# Sheet1.net
KiCad netlist of a schematic drawn in Altium Designer
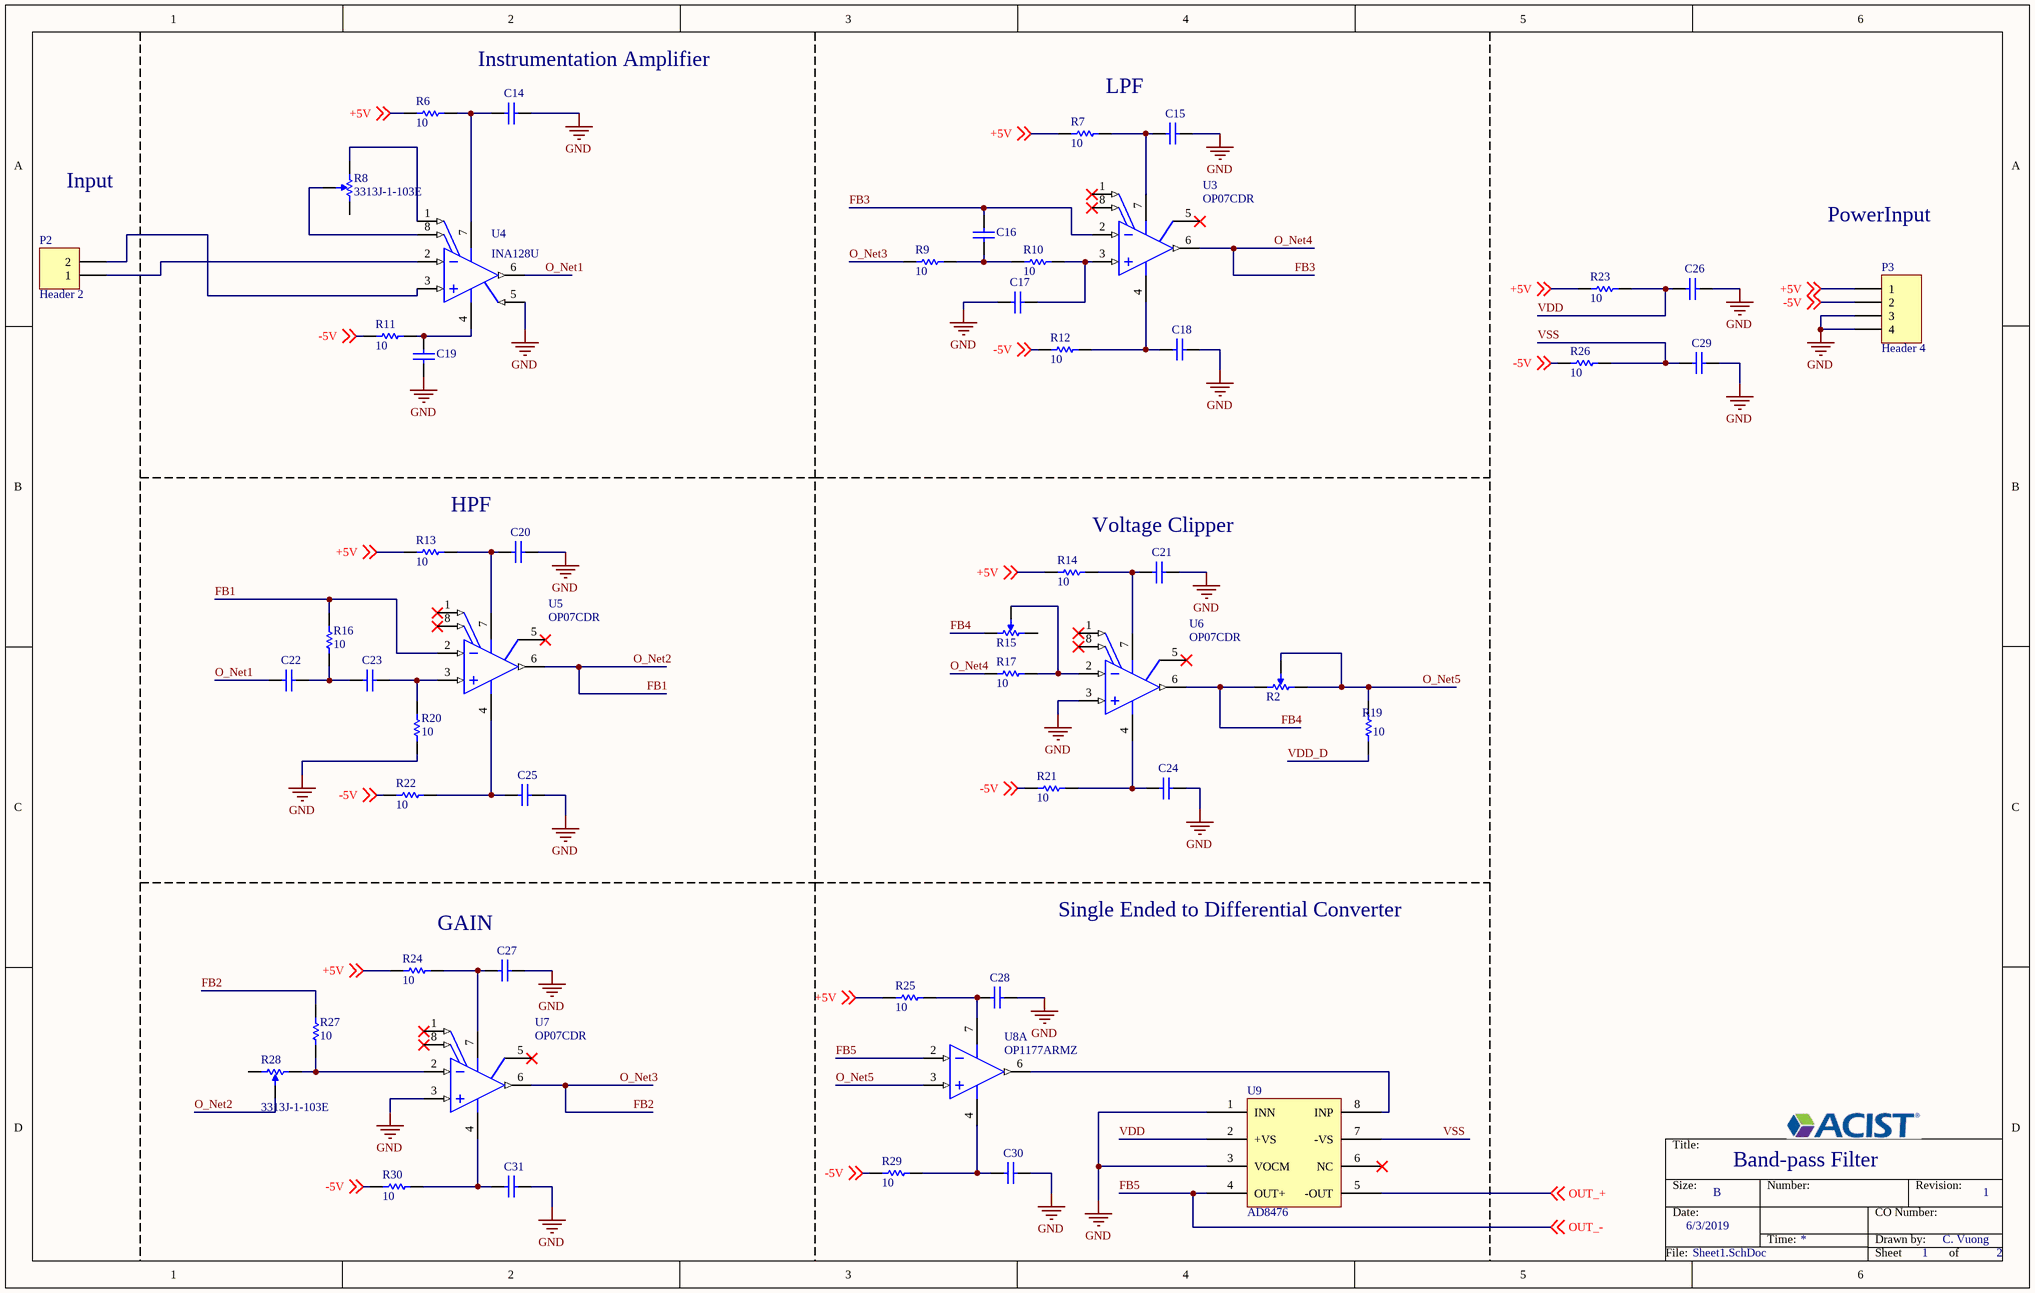
[diagram p0: Sheet1.SchDoc]

(export (version "E")
  (design (tool "Eeschema 10.0.6"))
  (components
    (comp (ref "C14")
      (value "C1608X5R1A106K080AC")
      (footprint "CAPC1608X90X20ML10")
      (description "Chip Capacitor, 10 uF, +/- 10%, 10 V, -55 to 85 degC, 0603 (1608 Metric), RoHS, Tape and Reel")
      (fields
        (field (name "PCN PART NUMBER") "MLCCPartNumberChange30/Nov/2012")
        (field (name "TOLERANCE") "±10%")
      )
      (libsource (lib "Altium Content Vault") (part "CAP-NP-2"))
    )
    (comp (ref "C15")
      (value "C1608X5R1A106K080AC")
      (footprint "CAPC1608X90X20ML10")
      (description "Chip Capacitor, 10 uF, +/- 10%, 10 V, -55 to 85 degC, 0603 (1608 Metric), RoHS, Tape and Reel")
      (fields
        (field (name "PCN PART NUMBER") "MLCCPartNumberChange30/Nov/2012")
        (field (name "TOLERANCE") "±10%")
      )
      (libsource (lib "Altium Content Vault") (part "CAP-NP-2"))
    )
    (comp (ref "C16")
      (value "C1608X5R1A106K080AC")
      (footprint "CAPC1608X90X20ML10")
      (description "Chip Capacitor, 10 uF, +/- 10%, 10 V, -55 to 85 degC, 0603 (1608 Metric), RoHS, Tape and Reel")
      (fields
        (field (name "PCN PART NUMBER") "MLCCPartNumberChange30/Nov/2012")
        (field (name "TOLERANCE") "±10%")
      )
      (libsource (lib "Altium Content Vault") (part "CAP-NP-2"))
    )
    (comp (ref "C17")
      (value "C1608X5R1A106K080AC")
      (footprint "CAPC1608X90X20ML10")
      (description "Chip Capacitor, 10 uF, +/- 10%, 10 V, -55 to 85 degC, 0603 (1608 Metric), RoHS, Tape and Reel")
      (fields
        (field (name "PCN PART NUMBER") "MLCCPartNumberChange30/Nov/2012")
        (field (name "TOLERANCE") "±10%")
      )
      (libsource (lib "Altium Content Vault") (part "CAP-NP-2"))
    )
    (comp (ref "C18")
      (value "C1608X5R1A106K080AC")
      (footprint "CAPC1608X90X20ML10")
      (description "Chip Capacitor, 10 uF, +/- 10%, 10 V, -55 to 85 degC, 0603 (1608 Metric), RoHS, Tape and Reel")
      (fields
        (field (name "PCN PART NUMBER") "MLCCPartNumberChange30/Nov/2012")
        (field (name "TOLERANCE") "±10%")
      )
      (libsource (lib "Altium Content Vault") (part "CAP-NP-2"))
    )
    (comp (ref "C19")
      (value "C1608X5R1A106K080AC")
      (footprint "CAPC1608X90X20ML10")
      (description "Chip Capacitor, 10 uF, +/- 10%, 10 V, -55 to 85 degC, 0603 (1608 Metric), RoHS, Tape and Reel")
      (fields
        (field (name "PCN PART NUMBER") "MLCCPartNumberChange30/Nov/2012")
        (field (name "TOLERANCE") "±10%")
      )
      (libsource (lib "Altium Content Vault") (part "CAP-NP-2"))
    )
    (comp (ref "C20")
      (value "C1608X5R1A106K080AC")
      (footprint "CAPC1608X90X20ML10")
      (description "Chip Capacitor, 10 uF, +/- 10%, 10 V, -55 to 85 degC, 0603 (1608 Metric), RoHS, Tape and Reel")
      (fields
        (field (name "PCN PART NUMBER") "MLCCPartNumberChange30/Nov/2012")
        (field (name "TOLERANCE") "±10%")
      )
      (libsource (lib "Altium Content Vault") (part "CAP-NP-2"))
    )
    (comp (ref "C21")
      (value "C1608X5R1A106K080AC")
      (footprint "CAPC1608X90X20ML10")
      (description "Chip Capacitor, 10 uF, +/- 10%, 10 V, -55 to 85 degC, 0603 (1608 Metric), RoHS, Tape and Reel")
      (fields
        (field (name "PCN PART NUMBER") "MLCCPartNumberChange30/Nov/2012")
        (field (name "TOLERANCE") "±10%")
      )
      (libsource (lib "Altium Content Vault") (part "CAP-NP-2"))
    )
    (comp (ref "C22")
      (value "C1608X5R1A106K080AC")
      (footprint "CAPC1608X90X20ML10")
      (description "Chip Capacitor, 10 uF, +/- 10%, 10 V, -55 to 85 degC, 0603 (1608 Metric), RoHS, Tape and Reel")
      (fields
        (field (name "PCN PART NUMBER") "MLCCPartNumberChange30/Nov/2012")
        (field (name "TOLERANCE") "±10%")
      )
      (libsource (lib "Altium Content Vault") (part "CAP-NP-2"))
    )
    (comp (ref "C23")
      (value "C1608X5R1A106K080AC")
      (footprint "CAPC1608X90X20ML10")
      (description "Chip Capacitor, 10 uF, +/- 10%, 10 V, -55 to 85 degC, 0603 (1608 Metric), RoHS, Tape and Reel")
      (fields
        (field (name "PCN PART NUMBER") "MLCCPartNumberChange30/Nov/2012")
        (field (name "TOLERANCE") "±10%")
      )
      (libsource (lib "Altium Content Vault") (part "CAP-NP-2"))
    )
    (comp (ref "C24")
      (value "C1608X5R1A106K080AC")
      (footprint "CAPC1608X90X20ML10")
      (description "Chip Capacitor, 10 uF, +/- 10%, 10 V, -55 to 85 degC, 0603 (1608 Metric), RoHS, Tape and Reel")
      (fields
        (field (name "PCN PART NUMBER") "MLCCPartNumberChange30/Nov/2012")
        (field (name "TOLERANCE") "±10%")
      )
      (libsource (lib "Altium Content Vault") (part "CAP-NP-2"))
    )
    (comp (ref "C25")
      (value "C1608X5R1A106K080AC")
      (footprint "CAPC1608X90X20ML10")
      (description "Chip Capacitor, 10 uF, +/- 10%, 10 V, -55 to 85 degC, 0603 (1608 Metric), RoHS, Tape and Reel")
      (fields
        (field (name "PCN PART NUMBER") "MLCCPartNumberChange30/Nov/2012")
        (field (name "TOLERANCE") "±10%")
      )
      (libsource (lib "Altium Content Vault") (part "CAP-NP-2"))
    )
    (comp (ref "C26")
      (value "C1608X5R1A106K080AC")
      (footprint "CAPC1608X90X20ML10")
      (description "Chip Capacitor, 10 uF, +/- 10%, 10 V, -55 to 85 degC, 0603 (1608 Metric), RoHS, Tape and Reel")
      (fields
        (field (name "PCN PART NUMBER") "MLCCPartNumberChange30/Nov/2012")
        (field (name "TOLERANCE") "±10%")
      )
      (libsource (lib "Altium Content Vault") (part "CAP-NP-2"))
    )
    (comp (ref "C27")
      (value "C1608X5R1A106K080AC")
      (footprint "CAPC1608X90X20ML10")
      (description "Chip Capacitor, 10 uF, +/- 10%, 10 V, -55 to 85 degC, 0603 (1608 Metric), RoHS, Tape and Reel")
      (fields
        (field (name "PCN PART NUMBER") "MLCCPartNumberChange30/Nov/2012")
        (field (name "TOLERANCE") "±10%")
      )
      (libsource (lib "Altium Content Vault") (part "CAP-NP-2"))
    )
    (comp (ref "C28")
      (value "C1608X5R1A106K080AC")
      (footprint "CAPC1608X90X20ML10")
      (description "Chip Capacitor, 10 uF, +/- 10%, 10 V, -55 to 85 degC, 0603 (1608 Metric), RoHS, Tape and Reel")
      (fields
        (field (name "PCN PART NUMBER") "MLCCPartNumberChange30/Nov/2012")
        (field (name "TOLERANCE") "±10%")
      )
      (libsource (lib "Altium Content Vault") (part "CAP-NP-2"))
    )
    (comp (ref "C29")
      (value "C1608X5R1A106K080AC")
      (footprint "CAPC1608X90X20ML10")
      (description "Chip Capacitor, 10 uF, +/- 10%, 10 V, -55 to 85 degC, 0603 (1608 Metric), RoHS, Tape and Reel")
      (fields
        (field (name "PCN PART NUMBER") "MLCCPartNumberChange30/Nov/2012")
        (field (name "TOLERANCE") "±10%")
      )
      (libsource (lib "Altium Content Vault") (part "CAP-NP-2"))
    )
    (comp (ref "C30")
      (value "C1608X5R1A106K080AC")
      (footprint "CAPC1608X90X20ML10")
      (description "Chip Capacitor, 10 uF, +/- 10%, 10 V, -55 to 85 degC, 0603 (1608 Metric), RoHS, Tape and Reel")
      (fields
        (field (name "PCN PART NUMBER") "MLCCPartNumberChange30/Nov/2012")
        (field (name "TOLERANCE") "±10%")
      )
      (libsource (lib "Altium Content Vault") (part "CAP-NP-2"))
    )
    (comp (ref "C31")
      (value "C1608X5R1A106K080AC")
      (footprint "CAPC1608X90X20ML10")
      (description "Chip Capacitor, 10 uF, +/- 10%, 10 V, -55 to 85 degC, 0603 (1608 Metric), RoHS, Tape and Reel")
      (fields
        (field (name "PCN PART NUMBER") "MLCCPartNumberChange30/Nov/2012")
        (field (name "TOLERANCE") "±10%")
      )
      (libsource (lib "Altium Content Vault") (part "CAP-NP-2"))
    )
    (comp (ref "P2")
      (value "Header 2")
      (footprint "HDR1X2")
      (description "Header, 2-Pin")
      (fields (field (name "PUBLISHER") "Altium Limited"))
      (libsource (lib "Miscellaneous Connectors") (part "Header 2"))
    )
    (comp (ref "P3")
      (value "Header 4")
      (footprint "HDR1X4")
      (description "Header, 4-Pin")
      (fields (field (name "PUBLISHER") "Altium Limited"))
      (libsource (lib "Miscellaneous Connectors") (part "Header 4"))
    )
    (comp (ref "R2")
      (value "3313J-1-103E")
      (footprint "BOUR-3313J-1_V")
      (description "Trimming Potentiometer, 10 KOhm, -55 to 125 degC, 3-Pin SMD, RoHS, Tape and Reel")
      (fields (field (name "MANUFACTURER") "Bourns"))
      (libsource (lib "Altium Content Vault") (part "RES-ADJ-3_A"))
    )
    (comp (ref "R6")
      (value "10")
      (footprint "RESC1608X50X30LL20T20")
      (fields (field (name "PART NUMBER") "RR0816P-241-D") (field (name "MANUFACTURER") "Susumu"))
      (libsource (lib "Altium Content Vault") (part "RES"))
    )
    (comp (ref "R7")
      (value "10")
      (footprint "RESC1608X50X30LL20T20")
      (fields (field (name "PART NUMBER") "RR0816P-241-D") (field (name "MANUFACTURER") "Susumu"))
      (libsource (lib "Altium Content Vault") (part "RES"))
    )
    (comp (ref "R8")
      (value "3313J-1-103E")
      (footprint "BOUR-3313J-1_V")
      (description "Trimming Potentiometer, 10 KOhm, -55 to 125 degC, 3-Pin SMD, RoHS, Tape and Reel")
      (fields (field (name "MANUFACTURER") "Bourns"))
      (libsource (lib "Altium Content Vault") (part "RES-ADJ-3_A"))
    )
    (comp (ref "R9")
      (value "10")
      (footprint "RESC1608X50X30LL20T20")
      (fields (field (name "PART NUMBER") "RR0816P-241-D") (field (name "MANUFACTURER") "Susumu"))
      (libsource (lib "Altium Content Vault") (part "RES"))
    )
    (comp (ref "R10")
      (value "10")
      (footprint "RESC1608X50X30LL20T20")
      (fields (field (name "PART NUMBER") "RR0816P-241-D") (field (name "MANUFACTURER") "Susumu"))
      (libsource (lib "Altium Content Vault") (part "RES"))
    )
    (comp (ref "R11")
      (value "10")
      (footprint "RESC1608X50X30LL20T20")
      (fields (field (name "PART NUMBER") "RR0816P-241-D") (field (name "MANUFACTURER") "Susumu"))
      (libsource (lib "Altium Content Vault") (part "RES"))
    )
    (comp (ref "R12")
      (value "10")
      (footprint "RESC1608X50X30LL20T20")
      (fields (field (name "PART NUMBER") "RR0816P-241-D") (field (name "MANUFACTURER") "Susumu"))
      (libsource (lib "Altium Content Vault") (part "RES"))
    )
    (comp (ref "R13")
      (value "10")
      (footprint "RESC1608X50X30LL20T20")
      (fields (field (name "PART NUMBER") "RR0816P-241-D") (field (name "MANUFACTURER") "Susumu"))
      (libsource (lib "Altium Content Vault") (part "RES"))
    )
    (comp (ref "R14")
      (value "10")
      (footprint "RESC1608X50X30LL20T20")
      (fields (field (name "PART NUMBER") "RR0816P-241-D") (field (name "MANUFACTURER") "Susumu"))
      (libsource (lib "Altium Content Vault") (part "RES"))
    )
    (comp (ref "R15")
      (value "3313J-1-103E")
      (footprint "BOUR-3313J-1_V")
      (description "Trimming Potentiometer, 10 KOhm, -55 to 125 degC, 3-Pin SMD, RoHS, Tape and Reel")
      (fields (field (name "MANUFACTURER") "Bourns"))
      (libsource (lib "Altium Content Vault") (part "RES-ADJ-3_A"))
    )
    (comp (ref "R16")
      (value "10")
      (footprint "RESC1608X50X30LL20T20")
      (fields (field (name "PART NUMBER") "RR0816P-241-D") (field (name "MANUFACTURER") "Susumu"))
      (libsource (lib "Altium Content Vault") (part "RES"))
    )
    (comp (ref "R17")
      (value "10")
      (footprint "RESC1608X50X30LL20T20")
      (fields (field (name "PART NUMBER") "RR0816P-241-D") (field (name "MANUFACTURER") "Susumu"))
      (libsource (lib "Altium Content Vault") (part "RES"))
    )
    (comp (ref "R19")
      (value "10")
      (footprint "RESC1608X50X30LL20T20")
      (fields (field (name "PART NUMBER") "RR0816P-241-D") (field (name "MANUFACTURER") "Susumu"))
      (libsource (lib "Altium Content Vault") (part "RES"))
    )
    (comp (ref "R20")
      (value "10")
      (footprint "RESC1608X50X30LL20T20")
      (fields (field (name "PART NUMBER") "RR0816P-241-D") (field (name "MANUFACTURER") "Susumu"))
      (libsource (lib "Altium Content Vault") (part "RES"))
    )
    (comp (ref "R21")
      (value "10")
      (footprint "RESC1608X50X30LL20T20")
      (fields (field (name "PART NUMBER") "RR0816P-241-D") (field (name "MANUFACTURER") "Susumu"))
      (libsource (lib "Altium Content Vault") (part "RES"))
    )
    (comp (ref "R22")
      (value "10")
      (footprint "RESC1608X50X30LL20T20")
      (fields (field (name "PART NUMBER") "RR0816P-241-D") (field (name "MANUFACTURER") "Susumu"))
      (libsource (lib "Altium Content Vault") (part "RES"))
    )
    (comp (ref "R23")
      (value "10")
      (footprint "RESC1608X50X30LL20T20")
      (fields (field (name "PART NUMBER") "RR0816P-241-D") (field (name "MANUFACTURER") "Susumu"))
      (libsource (lib "Altium Content Vault") (part "RES"))
    )
    (comp (ref "R24")
      (value "10")
      (footprint "RESC1608X50X30LL20T20")
      (fields (field (name "PART NUMBER") "RR0816P-241-D") (field (name "MANUFACTURER") "Susumu"))
      (libsource (lib "Altium Content Vault") (part "RES"))
    )
    (comp (ref "R25")
      (value "10")
      (footprint "RESC1608X50X30LL20T20")
      (fields (field (name "PART NUMBER") "RR0816P-241-D") (field (name "MANUFACTURER") "Susumu"))
      (libsource (lib "Altium Content Vault") (part "RES"))
    )
    (comp (ref "R26")
      (value "10")
      (footprint "RESC1608X50X30LL20T20")
      (fields (field (name "PART NUMBER") "RR0816P-241-D") (field (name "MANUFACTURER") "Susumu"))
      (libsource (lib "Altium Content Vault") (part "RES"))
    )
    (comp (ref "R27")
      (value "10")
      (footprint "RESC1608X50X30LL20T20")
      (fields (field (name "PART NUMBER") "RR0816P-241-D") (field (name "MANUFACTURER") "Susumu"))
      (libsource (lib "Altium Content Vault") (part "RES"))
    )
    (comp (ref "R28")
      (value "3313J-1-103E")
      (footprint "BOUR-3313J-1_V")
      (description "Trimming Potentiometer, 10 KOhm, -55 to 125 degC, 3-Pin SMD, RoHS, Tape and Reel")
      (fields (field (name "MANUFACTURER") "Bourns"))
      (libsource (lib "Altium Content Vault") (part "RES-ADJ-3_A"))
    )
    (comp (ref "R29")
      (value "10")
      (footprint "RESC1608X50X30LL20T20")
      (fields (field (name "PART NUMBER") "RR0816P-241-D") (field (name "MANUFACTURER") "Susumu"))
      (libsource (lib "Altium Content Vault") (part "RES"))
    )
    (comp (ref "R30")
      (value "10")
      (footprint "RESC1608X50X30LL20T20")
      (fields (field (name "PART NUMBER") "RR0816P-241-D") (field (name "MANUFACTURER") "Susumu"))
      (libsource (lib "Altium Content Vault") (part "RES"))
    )
    (comp (ref "U3")
      (value "OP07CDR")
      (footprint "D0008A_M")
      (fields (field (name "MANUFACTURER") "Texas Instruments"))
      (libsource (lib "Altium Content Vault") (part "TI-OP07X-X8"))
    )
    (comp (ref "U4")
      (value "INA128U")
      (footprint "D0008A_N")
      (fields (field (name "MANUFACTURER") "Texas Instruments"))
      (libsource (lib "Altium Content Vault") (part "TI-INA1XX-8"))
    )
    (comp (ref "U5")
      (value "OP07CDR")
      (footprint "D0008A_M")
      (fields (field (name "MANUFACTURER") "Texas Instruments"))
      (libsource (lib "Altium Content Vault") (part "TI-OP07X-X8"))
    )
    (comp (ref "U6")
      (value "OP07CDR")
      (footprint "D0008A_M")
      (fields (field (name "MANUFACTURER") "Texas Instruments"))
      (libsource (lib "Altium Content Vault") (part "TI-OP07X-X8"))
    )
    (comp (ref "U7")
      (value "OP07CDR")
      (footprint "D0008A_M")
      (fields (field (name "MANUFACTURER") "Texas Instruments"))
      (libsource (lib "Altium Content Vault") (part "TI-OP07X-X8"))
    )
    (comp (ref "U8")
      (value "OP1177ARMZ")
      (footprint "ADI-RM-8_M")
      (fields (field (name "GENERIC PART NUMBER") "OP1177") (field (name "MANUFACTURER") "Analog Devices"))
      (libsource (lib "Project X") (part "ADI-AD_ADA_OPXXXX-X-8"))
    )
    (comp (ref "U9") (value "AD8476") (footprint "MSOP8") (libsource (lib "Project X") (part "AD8476")))
  )
  (nets
    (net (code "1") (name "+5V") (class "Default")
      (node (ref "P3") (pin "1") (pinfunction "1_1") (pintype "passive"))
      (node (ref "R13") (pin "2") (pinfunction "2_2") (pintype "passive"))
      (node (ref "R14") (pin "2") (pinfunction "2_2") (pintype "passive"))
      (node (ref "R23") (pin "2") (pinfunction "2_2") (pintype "passive"))
      (node (ref "R24") (pin "2") (pinfunction "2_2") (pintype "passive"))
      (node (ref "R25") (pin "2") (pinfunction "2_2") (pintype "passive"))
      (node (ref "R6") (pin "2") (pinfunction "2_2") (pintype "passive"))
      (node (ref "R7") (pin "2") (pinfunction "2_2") (pintype "passive"))
    )
    (net (code "2") (name "-5V") (class "Default")
      (node (ref "P3") (pin "2") (pinfunction "2_2") (pintype "passive"))
      (node (ref "R11") (pin "2") (pinfunction "2_2") (pintype "passive"))
      (node (ref "R12") (pin "2") (pinfunction "2_2") (pintype "passive"))
      (node (ref "R21") (pin "2") (pinfunction "2_2") (pintype "passive"))
      (node (ref "R22") (pin "2") (pinfunction "2_2") (pintype "passive"))
      (node (ref "R26") (pin "2") (pinfunction "2_2") (pintype "passive"))
      (node (ref "R29") (pin "2") (pinfunction "2_2") (pintype "passive"))
      (node (ref "R30") (pin "2") (pinfunction "2_2") (pintype "passive"))
    )
    (net (code "3") (name "/FB1") (class "Default")
      (node (ref "R16") (pin "1") (pinfunction "1_1") (pintype "passive"))
      (node (ref "R28") (pin "2") (pinfunction "2_2") (pintype "passive"))
      (node (ref "U5") (pin "2") (pinfunction "IN-_2") (pintype "input"))
      (node (ref "U5") (pin "6") (pinfunction "OUT_6") (pintype "output"))
    )
    (net (code "4") (name "/FB2") (class "Default")
      (node (ref "R27") (pin "1") (pinfunction "1_1") (pintype "passive"))
      (node (ref "R9") (pin "2") (pinfunction "2_2") (pintype "passive"))
      (node (ref "U7") (pin "6") (pinfunction "OUT_6") (pintype "output"))
    )
    (net (code "5") (name "/FB3") (class "Default")
      (node (ref "C16") (pin "1") (pinfunction "1_1") (pintype "passive"))
      (node (ref "R17") (pin "2") (pinfunction "2_2") (pintype "passive"))
      (node (ref "U3") (pin "2") (pinfunction "IN-_2") (pintype "input"))
      (node (ref "U3") (pin "6") (pinfunction "OUT_6") (pintype "output"))
    )
    (net (code "6") (name "/FB4") (class "Default")
      (node (ref "R15") (pin "3") (pinfunction "3_3") (pintype "passive"))
      (node (ref "R2") (pin "3") (pinfunction "3_3") (pintype "passive"))
      (node (ref "U6") (pin "6") (pinfunction "OUT_6") (pintype "output"))
    )
    (net (code "7") (name "/O_Net1") (class "Default")
      (node (ref "C22") (pin "2") (pinfunction "2_2") (pintype "passive"))
      (node (ref "U4") (pin "6") (pinfunction "VO_6") (pintype "output"))
    )
    (net (code "8") (name "/O_Net5") (class "Default")
      (node (ref "R19") (pin "1") (pinfunction "1_1") (pintype "passive"))
      (node (ref "R2") (pin "1") (pinfunction "1_1") (pintype "passive"))
      (node (ref "R2") (pin "2") (pinfunction "2_2") (pintype "passive"))
      (node (ref "U8") (pin "3") (pinfunction "+IN_3") (pintype "input"))
    )
    (net (code "9") (name "/VDD") (class "Default")
      (node (ref "C26") (pin "2") (pinfunction "2_2") (pintype "passive"))
      (node (ref "R23") (pin "1") (pinfunction "1_1") (pintype "passive"))
      (node (ref "U9") (pin "2") (pinfunction "+VS_2") (pintype "passive"))
    )
    (net (code "10") (name "/VDD_D") (class "Default")
      (node (ref "R19") (pin "2") (pinfunction "2_2") (pintype "passive"))
    )
    (net (code "11") (name "/VSS") (class "Default")
      (node (ref "C29") (pin "2") (pinfunction "2_2") (pintype "passive"))
      (node (ref "R26") (pin "1") (pinfunction "1_1") (pintype "passive"))
      (node (ref "U9") (pin "7") (pinfunction "-VS_7") (pintype "passive"))
    )
    (net (code "12") (name "GND") (class "Default")
      (node (ref "C14") (pin "1") (pinfunction "1_1") (pintype "passive"))
      (node (ref "C15") (pin "1") (pinfunction "1_1") (pintype "passive"))
      (node (ref "C17") (pin "1") (pinfunction "1_1") (pintype "passive"))
      (node (ref "C18") (pin "1") (pinfunction "1_1") (pintype "passive"))
      (node (ref "C19") (pin "1") (pinfunction "1_1") (pintype "passive"))
      (node (ref "C20") (pin "1") (pinfunction "1_1") (pintype "passive"))
      (node (ref "C21") (pin "1") (pinfunction "1_1") (pintype "passive"))
      (node (ref "C24") (pin "1") (pinfunction "1_1") (pintype "passive"))
      (node (ref "C25") (pin "1") (pinfunction "1_1") (pintype "passive"))
      (node (ref "C26") (pin "1") (pinfunction "1_1") (pintype "passive"))
      (node (ref "C27") (pin "1") (pinfunction "1_1") (pintype "passive"))
      (node (ref "C28") (pin "1") (pinfunction "1_1") (pintype "passive"))
      (node (ref "C29") (pin "1") (pinfunction "1_1") (pintype "passive"))
      (node (ref "C30") (pin "1") (pinfunction "1_1") (pintype "passive"))
      (node (ref "C31") (pin "1") (pinfunction "1_1") (pintype "passive"))
      (node (ref "P3") (pin "3") (pinfunction "3_3") (pintype "passive"))
      (node (ref "P3") (pin "4") (pinfunction "4_4") (pintype "passive"))
      (node (ref "R20") (pin "2") (pinfunction "2_2") (pintype "passive"))
      (node (ref "U4") (pin "5") (pinfunction "REF_5") (pintype "input"))
      (node (ref "U6") (pin "3") (pinfunction "IN+_3") (pintype "input"))
      (node (ref "U7") (pin "3") (pinfunction "IN+_3") (pintype "input"))
      (node (ref "U9") (pin "1") (pinfunction "INN_1") (pintype "passive"))
      (node (ref "U9") (pin "3") (pinfunction "VOCM_3") (pintype "passive"))
    )
    (net (code "13") (name "Net-(C16-Pad2)") (class "Default")
      (node (ref "C16") (pin "2") (pinfunction "2_2") (pintype "passive"))
      (node (ref "R10") (pin "2") (pinfunction "2_2") (pintype "passive"))
      (node (ref "R9") (pin "1") (pinfunction "1_1") (pintype "passive"))
    )
    (net (code "14") (name "Net-(C22-Pad1)") (class "Default")
      (node (ref "C22") (pin "1") (pinfunction "1_1") (pintype "passive"))
      (node (ref "C23") (pin "2") (pinfunction "2_2") (pintype "passive"))
      (node (ref "R16") (pin "2") (pinfunction "2_2") (pintype "passive"))
    )
    (net (code "15") (name "Net-(R8-Pad1)") (class "Default")
      (node (ref "R8") (pin "1") (pinfunction "1_1") (pintype "passive"))
      (node (ref "U4") (pin "1") (pinfunction "RG_1") (pintype "input"))
    )
    (net (code "16") (name "Net-(R8-Pad2)") (class "Default")
      (node (ref "R8") (pin "2") (pinfunction "2_2") (pintype "passive"))
      (node (ref "U4") (pin "8") (pinfunction "RG_8") (pintype "input"))
    )
    (net (code "17") (name "Net-(U3-IN+)") (class "Default")
      (node (ref "C17") (pin "2") (pinfunction "2_2") (pintype "passive"))
      (node (ref "R10") (pin "1") (pinfunction "1_1") (pintype "passive"))
      (node (ref "U3") (pin "3") (pinfunction "IN+_3") (pintype "input"))
    )
    (net (code "18") (name "Net-(U3-VCC+)") (class "Default")
      (node (ref "C15") (pin "2") (pinfunction "2_2") (pintype "passive"))
      (node (ref "R7") (pin "1") (pinfunction "1_1") (pintype "passive"))
      (node (ref "U3") (pin "7") (pinfunction "VCC+_7") (pintype "power_in"))
    )
    (net (code "19") (name "Net-(U3-VCC-)") (class "Default")
      (node (ref "C18") (pin "2") (pinfunction "2_2") (pintype "passive"))
      (node (ref "R12") (pin "1") (pinfunction "1_1") (pintype "passive"))
      (node (ref "U3") (pin "4") (pinfunction "VCC-_4") (pintype "power_in"))
    )
    (net (code "20") (name "Net-(U4-V+)") (class "Default")
      (node (ref "C14") (pin "2") (pinfunction "2_2") (pintype "passive"))
      (node (ref "R6") (pin "1") (pinfunction "1_1") (pintype "passive"))
      (node (ref "U4") (pin "7") (pinfunction "V+_7") (pintype "power_in"))
    )
    (net (code "21") (name "Net-(U4-V-)") (class "Default")
      (node (ref "C19") (pin "2") (pinfunction "2_2") (pintype "passive"))
      (node (ref "R11") (pin "1") (pinfunction "1_1") (pintype "passive"))
      (node (ref "U4") (pin "4") (pinfunction "V-_4") (pintype "power_in"))
    )
    (net (code "22") (name "Net-(U4-VIN+)") (class "Default")
      (node (ref "P2") (pin "2") (pinfunction "2_2") (pintype "passive"))
      (node (ref "U4") (pin "3") (pinfunction "VIN+_3") (pintype "input"))
    )
    (net (code "23") (name "Net-(U4-VIN-)") (class "Default")
      (node (ref "P2") (pin "1") (pinfunction "1_1") (pintype "passive"))
      (node (ref "U4") (pin "2") (pinfunction "VIN-_2") (pintype "input"))
    )
    (net (code "24") (name "Net-(U5-IN+)") (class "Default")
      (node (ref "C23") (pin "1") (pinfunction "1_1") (pintype "passive"))
      (node (ref "R20") (pin "1") (pinfunction "1_1") (pintype "passive"))
      (node (ref "U5") (pin "3") (pinfunction "IN+_3") (pintype "input"))
    )
    (net (code "25") (name "Net-(U5-VCC+)") (class "Default")
      (node (ref "C20") (pin "2") (pinfunction "2_2") (pintype "passive"))
      (node (ref "R13") (pin "1") (pinfunction "1_1") (pintype "passive"))
      (node (ref "U5") (pin "7") (pinfunction "VCC+_7") (pintype "power_in"))
    )
    (net (code "26") (name "Net-(U5-VCC-)") (class "Default")
      (node (ref "C25") (pin "2") (pinfunction "2_2") (pintype "passive"))
      (node (ref "R22") (pin "1") (pinfunction "1_1") (pintype "passive"))
      (node (ref "U5") (pin "4") (pinfunction "VCC-_4") (pintype "power_in"))
    )
    (net (code "27") (name "Net-(U6-IN-)") (class "Default")
      (node (ref "R15") (pin "2") (pinfunction "2_2") (pintype "passive"))
      (node (ref "R17") (pin "1") (pinfunction "1_1") (pintype "passive"))
      (node (ref "U6") (pin "2") (pinfunction "IN-_2") (pintype "input"))
    )
    (net (code "28") (name "Net-(U6-VCC+)") (class "Default")
      (node (ref "C21") (pin "2") (pinfunction "2_2") (pintype "passive"))
      (node (ref "R14") (pin "1") (pinfunction "1_1") (pintype "passive"))
      (node (ref "U6") (pin "7") (pinfunction "VCC+_7") (pintype "power_in"))
    )
    (net (code "29") (name "Net-(U6-VCC-)") (class "Default")
      (node (ref "C24") (pin "2") (pinfunction "2_2") (pintype "passive"))
      (node (ref "R21") (pin "1") (pinfunction "1_1") (pintype "passive"))
      (node (ref "U6") (pin "4") (pinfunction "VCC-_4") (pintype "power_in"))
    )
    (net (code "30") (name "Net-(U7-IN-)") (class "Default")
      (node (ref "R27") (pin "2") (pinfunction "2_2") (pintype "passive"))
      (node (ref "R28") (pin "3") (pinfunction "3_3") (pintype "passive"))
      (node (ref "U7") (pin "2") (pinfunction "IN-_2") (pintype "input"))
    )
    (net (code "31") (name "Net-(U7-VCC+)") (class "Default")
      (node (ref "C27") (pin "2") (pinfunction "2_2") (pintype "passive"))
      (node (ref "R24") (pin "1") (pinfunction "1_1") (pintype "passive"))
      (node (ref "U7") (pin "7") (pinfunction "VCC+_7") (pintype "power_in"))
    )
    (net (code "32") (name "Net-(U7-VCC-)") (class "Default")
      (node (ref "C31") (pin "2") (pinfunction "2_2") (pintype "passive"))
      (node (ref "R30") (pin "1") (pinfunction "1_1") (pintype "passive"))
      (node (ref "U7") (pin "4") (pinfunction "VCC-_4") (pintype "power_in"))
    )
    (net (code "33") (name "Net-(U8A-+V)") (class "Default")
      (node (ref "C28") (pin "2") (pinfunction "2_2") (pintype "passive"))
      (node (ref "R25") (pin "1") (pinfunction "1_1") (pintype "passive"))
      (node (ref "U8") (pin "7") (pinfunction "+V_7") (pintype "power_in"))
    )
    (net (code "34") (name "Net-(U8A--V)") (class "Default")
      (node (ref "C30") (pin "2") (pinfunction "2_2") (pintype "passive"))
      (node (ref "R29") (pin "1") (pinfunction "1_1") (pintype "passive"))
      (node (ref "U8") (pin "4") (pinfunction "-V_4") (pintype "power_in"))
    )
    (net (code "35") (name "Net-(U8A-OUT)") (class "Default")
      (node (ref "U8") (pin "6") (pinfunction "OUT_6") (pintype "output"))
      (node (ref "U9") (pin "8") (pinfunction "INP_8") (pintype "passive"))
    )
    (net (code "36") (name "OUT_+") (class "Default")
      (node (ref "U9") (pin "5") (pinfunction "-OUT_5") (pintype "passive"))
    )
    (net (code "37") (name "OUT_-") (class "Default")
      (node (ref "U8") (pin "2") (pinfunction "-IN_2") (pintype "input"))
      (node (ref "U9") (pin "4") (pinfunction "OUT+_4") (pintype "passive"))
    )
    (net (code "38") (name "unconnected-(R8-Pad3)") (class "Default")
      (node (ref "R8") (pin "3") (pinfunction "3_3") (pintype "passive"))
    )
    (net (code "39") (name "unconnected-(R15-Pad1)") (class "Default")
      (node (ref "R15") (pin "1") (pinfunction "1_1") (pintype "passive"))
    )
    (net (code "40") (name "unconnected-(R28-Pad1)") (class "Default")
      (node (ref "R28") (pin "1") (pinfunction "1_1") (pintype "passive"))
    )
    (net (code "41") (name "unconnected-(U3-NC-Pad5)") (class "Default")
      (node (ref "U3") (pin "5") (pinfunction "NC_5") (pintype "passive+no_connect"))
    )
    (net (code "42") (name "unconnected-(U3-OFFSET_N1-Pad1)") (class "Default")
      (node (ref "U3") (pin "1") (pinfunction "OFFSET_N1_1") (pintype "input+no_connect"))
    )
    (net (code "43") (name "unconnected-(U3-OFFSET_N2-Pad8)") (class "Default")
      (node (ref "U3") (pin "8") (pinfunction "OFFSET_N2_8") (pintype "input+no_connect"))
    )
    (net (code "44") (name "unconnected-(U5-NC-Pad5)") (class "Default")
      (node (ref "U5") (pin "5") (pinfunction "NC_5") (pintype "passive+no_connect"))
    )
    (net (code "45") (name "unconnected-(U5-OFFSET_N1-Pad1)") (class "Default")
      (node (ref "U5") (pin "1") (pinfunction "OFFSET_N1_1") (pintype "input+no_connect"))
    )
    (net (code "46") (name "unconnected-(U5-OFFSET_N2-Pad8)") (class "Default")
      (node (ref "U5") (pin "8") (pinfunction "OFFSET_N2_8") (pintype "input+no_connect"))
    )
    (net (code "47") (name "unconnected-(U6-NC-Pad5)") (class "Default")
      (node (ref "U6") (pin "5") (pinfunction "NC_5") (pintype "passive+no_connect"))
    )
    (net (code "48") (name "unconnected-(U6-OFFSET_N1-Pad1)") (class "Default")
      (node (ref "U6") (pin "1") (pinfunction "OFFSET_N1_1") (pintype "input+no_connect"))
    )
    (net (code "49") (name "unconnected-(U6-OFFSET_N2-Pad8)") (class "Default")
      (node (ref "U6") (pin "8") (pinfunction "OFFSET_N2_8") (pintype "input+no_connect"))
    )
    (net (code "50") (name "unconnected-(U7-NC-Pad5)") (class "Default")
      (node (ref "U7") (pin "5") (pinfunction "NC_5") (pintype "passive+no_connect"))
    )
    (net (code "51") (name "unconnected-(U7-OFFSET_N1-Pad1)") (class "Default")
      (node (ref "U7") (pin "1") (pinfunction "OFFSET_N1_1") (pintype "input+no_connect"))
    )
    (net (code "52") (name "unconnected-(U7-OFFSET_N2-Pad8)") (class "Default")
      (node (ref "U7") (pin "8") (pinfunction "OFFSET_N2_8") (pintype "input+no_connect"))
    )
    (net (code "53") (name "unconnected-(U9-NC-Pad6)") (class "Default")
      (node (ref "U9") (pin "6") (pinfunction "NC_6") (pintype "passive+no_connect"))
    )
  )
)
